# ETH1G_MAGNET_RJ45MIDMNT.net
KiCad netlist of a schematic drawn in Altium Designer
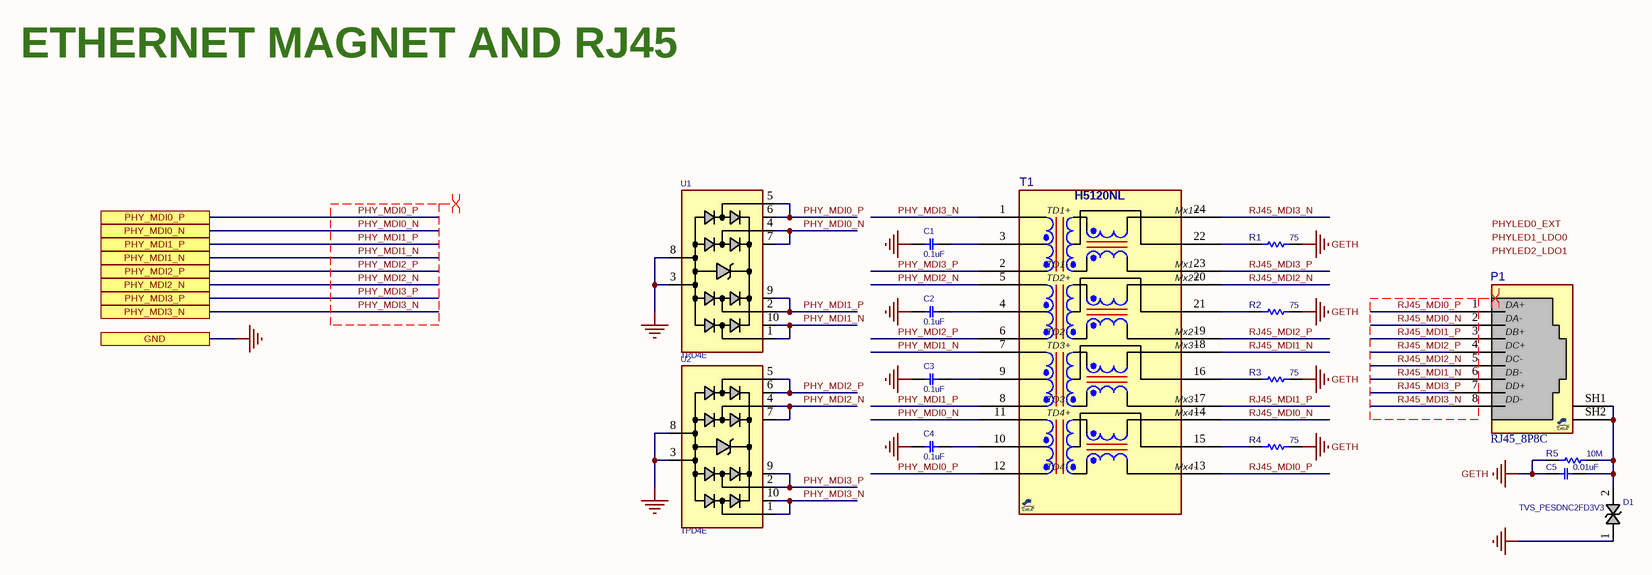
[diagram p0: ETH1G_MAGNET_RJ45MIDMNT.SchDoc]

(export (version "E")
  (design (tool "Eeschema 10.0.6"))
  (components
    (comp (ref "C1")
      (value "0.1uF")
      (footprint "C0402")
      (description "CAP, MLCC")
      (fields (field (name "MANF_P#") "GRM155R61E104") (field (name "MANF") "Murata"))
      (libsource (lib "mlcc_smd_passive") (part "CAP_SMD_MLCC_100n50T"))
    )
    (comp (ref "C2")
      (value "0.1uF")
      (footprint "C0402")
      (description "CAP, MLCC")
      (fields (field (name "MANF_P#") "GRM155R61E104") (field (name "MANF") "Murata"))
      (libsource (lib "mlcc_smd_passive") (part "CAP_SMD_MLCC_100n50T"))
    )
    (comp (ref "C3")
      (value "0.1uF")
      (footprint "C0402")
      (description "CAP, MLCC")
      (fields (field (name "MANF_P#") "GRM155R61E104") (field (name "MANF") "Murata"))
      (libsource (lib "mlcc_smd_passive") (part "CAP_SMD_MLCC_100n50T"))
    )
    (comp (ref "C4")
      (value "0.1uF")
      (footprint "C0402")
      (description "CAP, MLCC")
      (fields (field (name "MANF_P#") "GRM155R61E104") (field (name "MANF") "Murata"))
      (libsource (lib "mlcc_smd_passive") (part "CAP_SMD_MLCC_100n50T"))
    )
    (comp (ref "C5")
      (value "0.01uF")
      (footprint "C1210")
      (description "CAP, MLCC")
      (libsource (lib "mlcc_smd_passive") (part "CAP_SMD_MLCC_100n50T"))
    )
    (comp (ref "D1")
      (value "TVS_PESDNC2FD3V3")
      (footprint "ESD0402")
      (description "TVS, ESD PROTECT, Bidirectional")
      (fields (field (name "MANF_P#") "PESDNC2FD3V3BS"))
      (libsource (lib "protect_tvs_esd_fuse") (part "TVS_PESDNC2FD3V3"))
    )
    (comp (ref "P1")
      (value "RJ45_8P8C")
      (footprint "RJ45_8S_RA_TD_SMD")
      (description "RJ45, 8P, SHIELDED, RightAngle, TabDown, SMDEMI panel ground")
      (fields (field (name "MANF") "Heling") (field (name "MANF_P#") "MJ88-B011-JRVS1-P"))
      (libsource (lib "conn_rj_ModularJack") (part "RJ45_8S_RA_TD_SMD"))
    )
    (comp (ref "R1")
      (value "75")
      (footprint "R0402")
      (description "RESISTOR, SMD")
      (libsource (lib "passive_res_smd") (part "RES_SMD"))
    )
    (comp (ref "R2")
      (value "75")
      (footprint "R0402")
      (description "RESISTOR, SMD")
      (libsource (lib "passive_res_smd") (part "RES_SMD"))
    )
    (comp (ref "R3")
      (value "75")
      (footprint "R0402")
      (description "RESISTOR, SMD")
      (libsource (lib "passive_res_smd") (part "RES_SMD"))
    )
    (comp (ref "R4")
      (value "75")
      (footprint "R0402")
      (description "RESISTOR, SMD")
      (libsource (lib "passive_res_smd") (part "RES_SMD"))
    )
    (comp (ref "R5")
      (value "10M")
      (footprint "R1206")
      (description "RESISTOR, SMD")
      (libsource (lib "passive_res_smd") (part "RES_SMD"))
    )
    (comp (ref "T1")
      (value "H5120NL")
      (footprint "SO_24_9W2H")
      (description "Transformer, LAN, 1000 Base-T, 1CT:1CT, 350uH")
      (fields (field (name "MANF") "Pulse, link-pp") (field (name "MANF_P#") "H5120NL, LP82453NL"))
      (libsource (lib "transformer_ethernet") (part "H5120NL_SO24"))
    )
    (comp (ref "U1")
      (value "TPD4E")
      (footprint "SON50_10_2510")
      (description "TVS, ESD PROTECT, 4CH,")
      (fields (field (name "MANF_P#") "TPD4E05U06DQA") (field (name "MANF") "Texas Instruments"))
      (libsource (lib "protect_tvs_esd_fuse") (part "TVS_X4_TPD4E05U06"))
    )
    (comp (ref "U2")
      (value "TPD4E")
      (footprint "SON50_10_2510")
      (description "TVS, ESD PROTECT, 4CH,")
      (fields (field (name "MANF_P#") "TPD4E05U06DQA") (field (name "MANF") "Texas Instruments"))
      (libsource (lib "protect_tvs_esd_fuse") (part "TVS_X4_TPD4E05U06"))
    )
  )
  (nets
    (net (code "4") (name "/PHY_MDI0_N") (class "Default")
      (node (ref "T1") (pin "11") (pinfunction "TD4+_11") (pintype "passive"))
      (node (ref "U1") (pin "4") (pinfunction "4_4") (pintype "passive"))
      (node (ref "U1") (pin "7") (pinfunction "7_7") (pintype "passive"))
    )
    (net (code "5") (name "/PHY_MDI0_P") (class "Default")
      (node (ref "T1") (pin "12") (pinfunction "TD4-_12") (pintype "passive"))
      (node (ref "U1") (pin "5") (pinfunction "5_5") (pintype "passive"))
      (node (ref "U1") (pin "6") (pinfunction "6_6") (pintype "passive"))
    )
    (net (code "6") (name "/PHY_MDI1_N") (class "Default")
      (node (ref "T1") (pin "7") (pinfunction "TD3+_7") (pintype "passive"))
      (node (ref "U1") (pin "1") (pinfunction "1_1") (pintype "passive"))
      (node (ref "U1") (pin "10") (pinfunction "10_10") (pintype "passive"))
    )
    (net (code "7") (name "/PHY_MDI1_P") (class "Default")
      (node (ref "T1") (pin "8") (pinfunction "TD3-_8") (pintype "passive"))
      (node (ref "U1") (pin "2") (pinfunction "2_2") (pintype "passive"))
      (node (ref "U1") (pin "9") (pinfunction "9_9") (pintype "passive"))
    )
    (net (code "8") (name "/PHY_MDI2_N") (class "Default")
      (node (ref "T1") (pin "5") (pinfunction "TD2+_5") (pintype "passive"))
      (node (ref "U2") (pin "4") (pinfunction "4_4") (pintype "passive"))
      (node (ref "U2") (pin "7") (pinfunction "7_7") (pintype "passive"))
    )
    (net (code "9") (name "/PHY_MDI2_P") (class "Default")
      (node (ref "T1") (pin "6") (pinfunction "TD2-_6") (pintype "passive"))
      (node (ref "U2") (pin "5") (pinfunction "5_5") (pintype "passive"))
      (node (ref "U2") (pin "6") (pinfunction "6_6") (pintype "passive"))
    )
    (net (code "10") (name "/PHY_MDI3_N") (class "Default")
      (node (ref "T1") (pin "1") (pinfunction "TD1+_1") (pintype "passive"))
      (node (ref "U2") (pin "1") (pinfunction "1_1") (pintype "passive"))
      (node (ref "U2") (pin "10") (pinfunction "10_10") (pintype "passive"))
    )
    (net (code "11") (name "/PHY_MDI3_P") (class "Default")
      (node (ref "T1") (pin "2") (pinfunction "TD1-_2") (pintype "passive"))
      (node (ref "U2") (pin "2") (pinfunction "2_2") (pintype "passive"))
      (node (ref "U2") (pin "9") (pinfunction "9_9") (pintype "passive"))
    )
    (net (code "12") (name "/RJ45_MDI0_N") (class "Default")
      (node (ref "P1") (pin "2") (pinfunction "DA-_2") (pintype "passive"))
      (node (ref "T1") (pin "14") (pinfunction "MX4+_14") (pintype "passive"))
    )
    (net (code "13") (name "/RJ45_MDI0_P") (class "Default")
      (node (ref "P1") (pin "1") (pinfunction "DA+_1") (pintype "passive"))
      (node (ref "T1") (pin "13") (pinfunction "MX4-_13") (pintype "passive"))
    )
    (net (code "14") (name "/RJ45_MDI1_N") (class "Default")
      (node (ref "P1") (pin "6") (pinfunction "DB-_6") (pintype "passive"))
      (node (ref "T1") (pin "18") (pinfunction "MX3+_18") (pintype "passive"))
    )
    (net (code "15") (name "/RJ45_MDI1_P") (class "Default")
      (node (ref "P1") (pin "3") (pinfunction "DB+_3") (pintype "passive"))
      (node (ref "T1") (pin "17") (pinfunction "MX3-_17") (pintype "passive"))
    )
    (net (code "16") (name "/RJ45_MDI2_N") (class "Default")
      (node (ref "P1") (pin "5") (pinfunction "DC-_5") (pintype "passive"))
      (node (ref "T1") (pin "20") (pinfunction "MX2+_20") (pintype "passive"))
    )
    (net (code "17") (name "/RJ45_MDI2_P") (class "Default")
      (node (ref "P1") (pin "4") (pinfunction "DC+_4") (pintype "passive"))
      (node (ref "T1") (pin "19") (pinfunction "MX2-_19") (pintype "passive"))
    )
    (net (code "18") (name "/RJ45_MDI3_N") (class "Default")
      (node (ref "P1") (pin "8") (pinfunction "DD-_8") (pintype "passive"))
      (node (ref "T1") (pin "24") (pinfunction "MX1+_24") (pintype "passive"))
    )
    (net (code "19") (name "/RJ45_MDI3_P") (class "Default")
      (node (ref "P1") (pin "7") (pinfunction "DD+_7") (pintype "passive"))
      (node (ref "T1") (pin "23") (pinfunction "MX1-_23") (pintype "passive"))
    )
    (net (code "20") (name "GETH") (class "Default")
      (node (ref "C5") (pin "1") (pinfunction "1_1") (pintype "passive"))
      (node (ref "R1") (pin "1") (pinfunction "1_1") (pintype "passive"))
      (node (ref "R2") (pin "1") (pinfunction "1_1") (pintype "passive"))
      (node (ref "R3") (pin "1") (pinfunction "1_1") (pintype "passive"))
      (node (ref "R4") (pin "1") (pinfunction "1_1") (pintype "passive"))
      (node (ref "R5") (pin "2") (pinfunction "2_2") (pintype "passive"))
    )
    (net (code "21") (name "GND") (class "Default")
      (node (ref "C1") (pin "1") (pinfunction "1_1") (pintype "passive"))
      (node (ref "C2") (pin "1") (pinfunction "1_1") (pintype "passive"))
      (node (ref "C3") (pin "1") (pinfunction "1_1") (pintype "passive"))
      (node (ref "C4") (pin "1") (pinfunction "1_1") (pintype "passive"))
      (node (ref "D1") (pin "1") (pinfunction "1_1") (pintype "passive"))
      (node (ref "U1") (pin "3") (pinfunction "3_3") (pintype "passive"))
      (node (ref "U1") (pin "8") (pinfunction "8_8") (pintype "passive"))
      (node (ref "U2") (pin "3") (pinfunction "3_3") (pintype "passive"))
      (node (ref "U2") (pin "8") (pinfunction "8_8") (pintype "passive"))
    )
    (net (code "22") (name "Net-(C5-Pad2)") (class "Default")
      (node (ref "C5") (pin "2") (pinfunction "2_2") (pintype "passive"))
      (node (ref "D1") (pin "2") (pinfunction "2_2") (pintype "passive"))
      (node (ref "P1") (pin "SH1") (pinfunction "SH1_SH1") (pintype "passive"))
      (node (ref "P1") (pin "SH2") (pinfunction "SH2_SH2") (pintype "passive"))
      (node (ref "R5") (pin "1") (pinfunction "1_1") (pintype "passive"))
    )
    (net (code "23") (name "Net-(T1-MCT1)") (class "Default")
      (node (ref "R1") (pin "2") (pinfunction "2_2") (pintype "passive"))
      (node (ref "T1") (pin "22") (pinfunction "MCT1_22") (pintype "passive"))
    )
    (net (code "24") (name "Net-(T1-MCT2)") (class "Default")
      (node (ref "R2") (pin "2") (pinfunction "2_2") (pintype "passive"))
      (node (ref "T1") (pin "21") (pinfunction "MCT2_21") (pintype "passive"))
    )
    (net (code "25") (name "Net-(T1-MCT3)") (class "Default")
      (node (ref "R3") (pin "2") (pinfunction "2_2") (pintype "passive"))
      (node (ref "T1") (pin "16") (pinfunction "MCT3_16") (pintype "passive"))
    )
    (net (code "26") (name "Net-(T1-MCT4)") (class "Default")
      (node (ref "R4") (pin "2") (pinfunction "2_2") (pintype "passive"))
      (node (ref "T1") (pin "15") (pinfunction "MCT4_15") (pintype "passive"))
    )
    (net (code "27") (name "Net-(T1-TCT1)") (class "Default")
      (node (ref "C1") (pin "2") (pinfunction "2_2") (pintype "passive"))
      (node (ref "T1") (pin "3") (pinfunction "TCT1_3") (pintype "passive"))
    )
    (net (code "28") (name "Net-(T1-TCT2)") (class "Default")
      (node (ref "C2") (pin "2") (pinfunction "2_2") (pintype "passive"))
      (node (ref "T1") (pin "4") (pinfunction "TCT2_4") (pintype "passive"))
    )
    (net (code "29") (name "Net-(T1-TCT3)") (class "Default")
      (node (ref "C3") (pin "2") (pinfunction "2_2") (pintype "passive"))
      (node (ref "T1") (pin "9") (pinfunction "TCT3_9") (pintype "passive"))
    )
    (net (code "30") (name "Net-(T1-TCT4)") (class "Default")
      (node (ref "C4") (pin "2") (pinfunction "2_2") (pintype "passive"))
      (node (ref "T1") (pin "10") (pinfunction "TCT4_10") (pintype "passive"))
    )
  )
)
